# 2_5V_regulator.net
KiCad netlist of a schematic drawn in Altium Designer
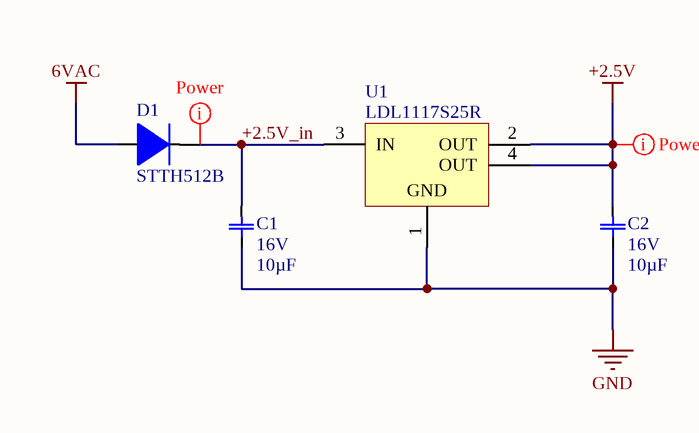
[diagram p0: 2.5V_regulator.SchDoc]

(export (version "E")
  (design (tool "Eeschema 10.0.6"))
  (components
    (comp (ref "C1")
      (value "10µF")
      (footprint "MLCC_1210")
      (description "MLCC 10µF 16V 1210")
      (fields (field (name "VOLTAGE") "16V"))
      (libsource (lib "Nixie") (part "MLCC 10µF 16V 1210"))
    )
    (comp (ref "C2")
      (value "10µF")
      (footprint "MLCC_1210")
      (description "MLCC 10µF 16V 1210")
      (fields (field (name "VOLTAGE") "16V"))
      (libsource (lib "Nixie") (part "MLCC 10µF 16V 1210"))
    )
    (comp (ref "D1")
      (value "STTH512B")
      (footprint "STTH512B")
      (description "Ultrafast recovery - 1200 V diode")
      (libsource (lib "Nixie") (part "STTH512B"))
    )
    (comp (ref "U1")
      (value "LDL1117S25R")
      (footprint "TLV1117")
      (description "Fixed LDO Voltage Regulator, 2.6 V to 18 V input, 75 mV Dropout, 2.5 V / 1.2 A out, SOT-223-4")
      (fields (field (name "MANUFACTURER") "Texas Instruments") (field (name "PARTNUMBER") "TLV1117LV25DCYT"))
      (libsource (lib "Nixie") (part "LDL1117S25R"))
    )
  )
  (nets
    (net (code "1") (name "+2.5V") (class "Default")
      (node (ref "C2") (pin "2") (pinfunction "2_2") (pintype "passive"))
      (node (ref "U1") (pin "2") (pinfunction "OUT_2") (pintype "power_in"))
      (node (ref "U1") (pin "4") (pinfunction "OUT_4") (pintype "power_in"))
    )
    (net (code "2") (name "/+2.5V_in") (class "Default")
      (node (ref "C1") (pin "2") (pinfunction "2_2") (pintype "passive"))
      (node (ref "D1") (pin "K") (pinfunction "K_K") (pintype "passive"))
      (node (ref "U1") (pin "3") (pinfunction "IN_3") (pintype "power_in"))
    )
    (net (code "3") (name "6VAC") (class "Default")
      (node (ref "D1") (pin "A") (pinfunction "A_A") (pintype "passive"))
    )
    (net (code "4") (name "GND") (class "Default")
      (node (ref "C1") (pin "1") (pinfunction "1_1") (pintype "passive"))
      (node (ref "C2") (pin "1") (pinfunction "1_1") (pintype "passive"))
      (node (ref "U1") (pin "1") (pinfunction "GND_1") (pintype "power_in"))
    )
  )
)
